# matrix_mixer_7eurorack.net
KiCad netlist of a schematic drawn in EAGLE
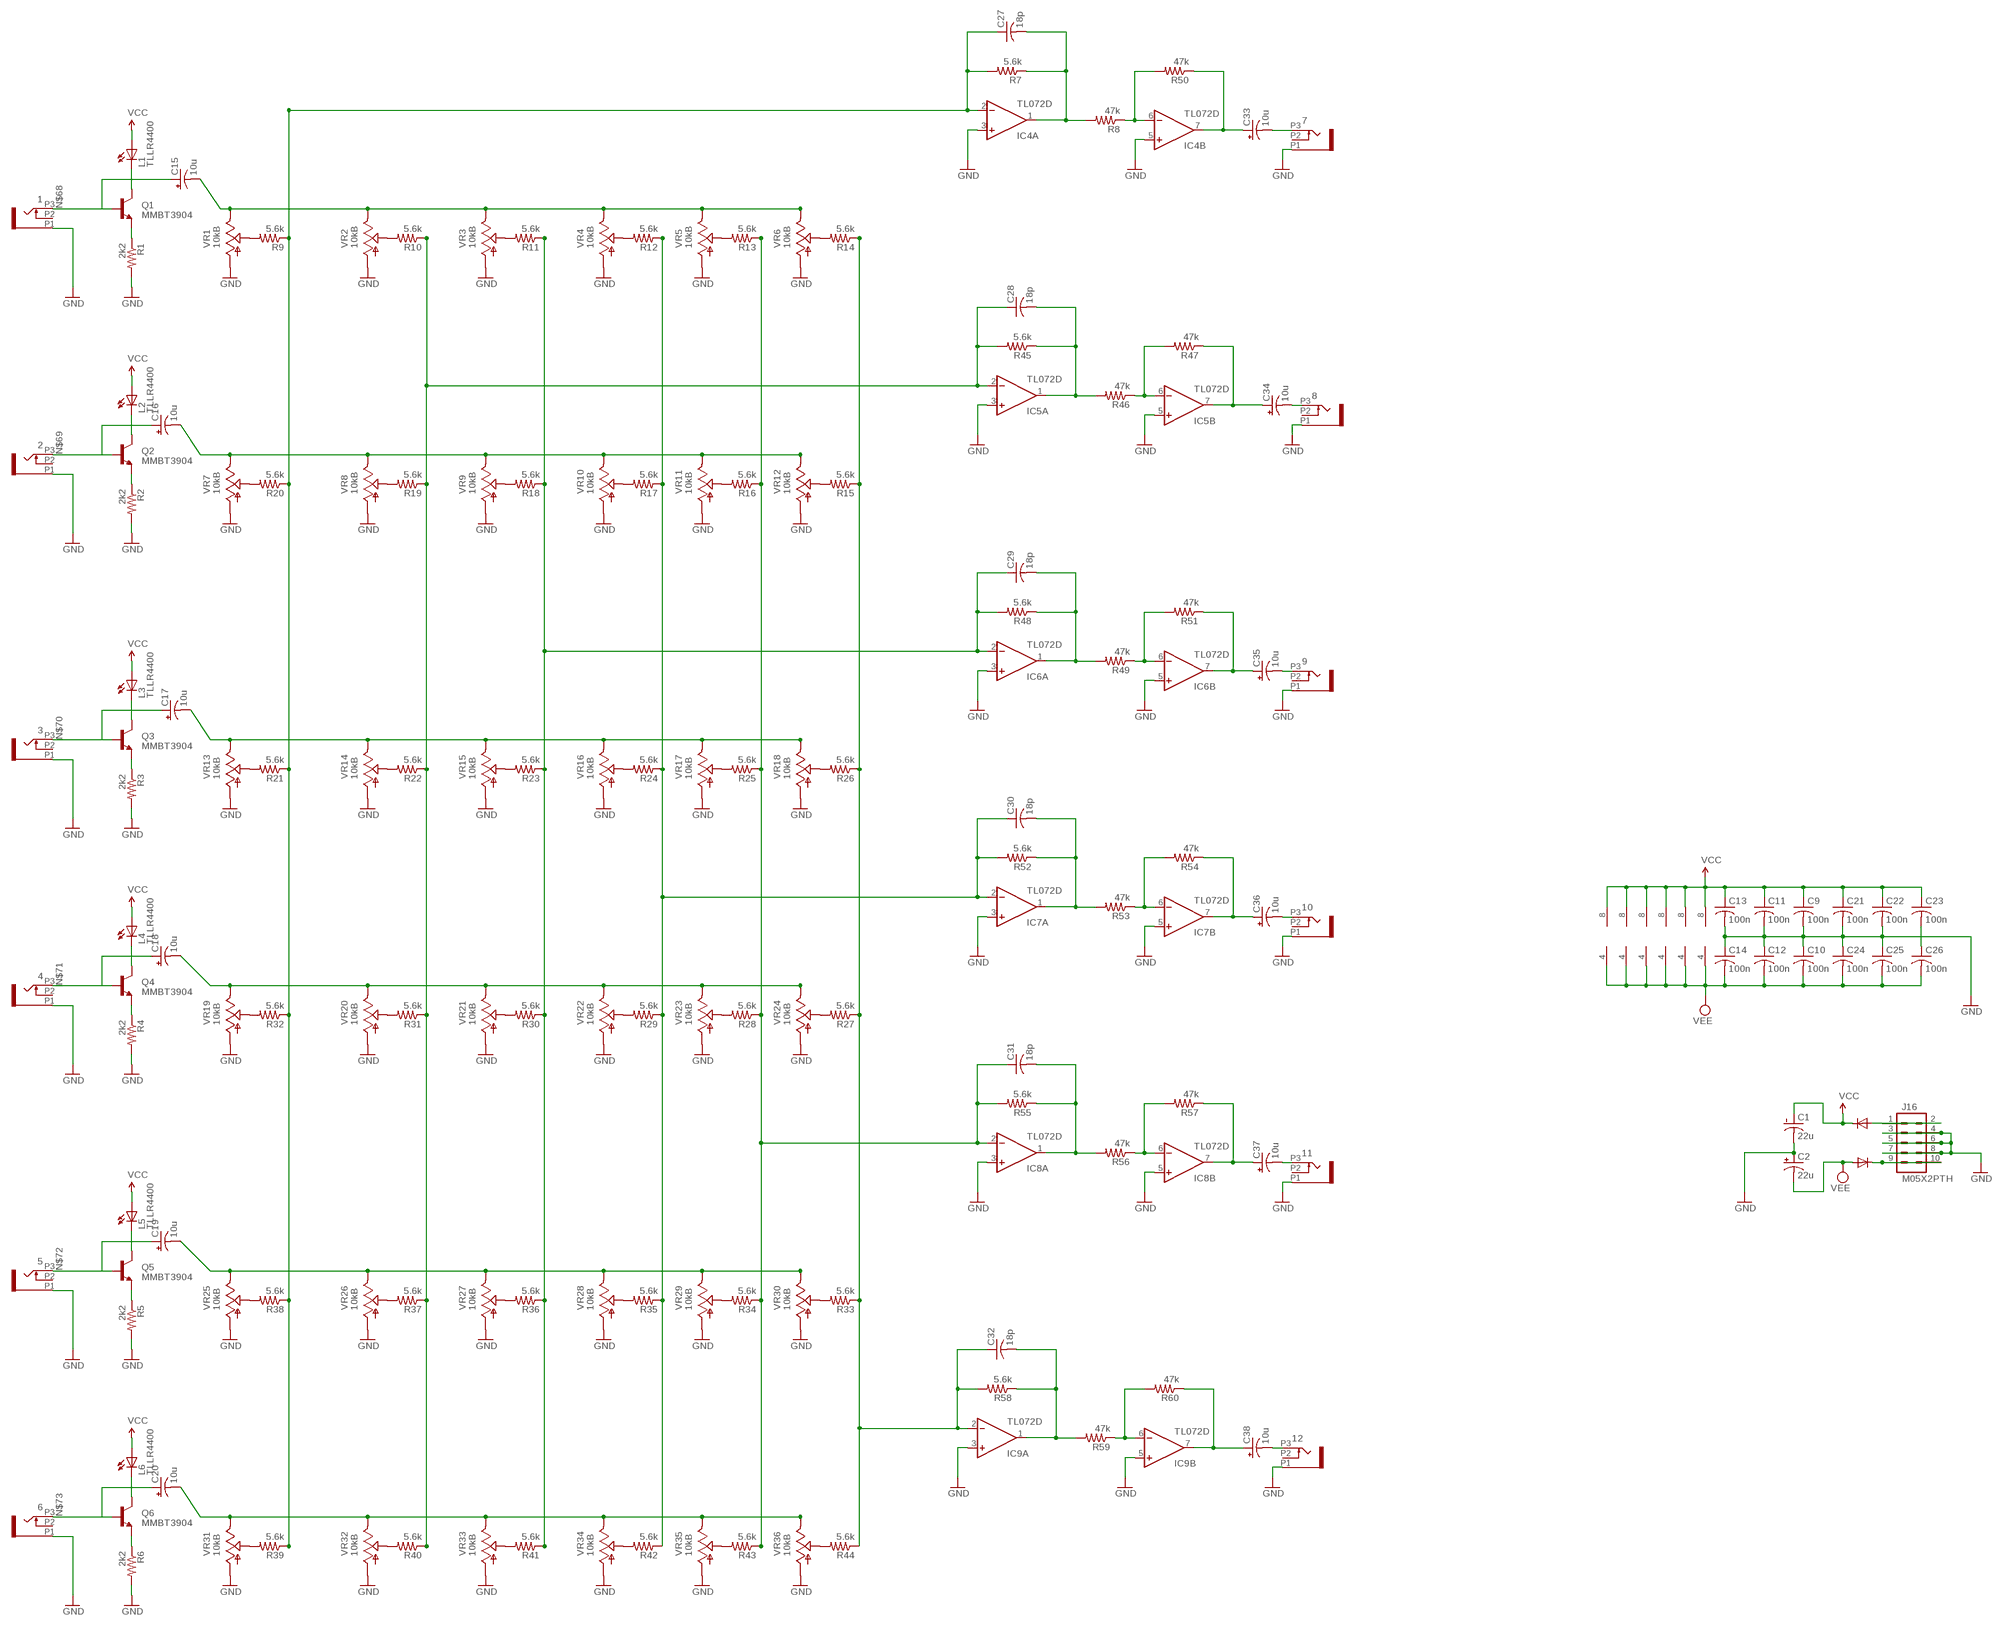
[diagram p0: schematic, sheet 1]

(export (version "E")
  (design (tool "Eeschema 10.0.6"))
  (components
    (comp (ref "1")
      (value "PJ301_THONKICONN6")
      (footprint "eagle-import:WQP_PJ_301M6")
      (libsource (lib "eagle-import") (part "PJ301_THONKICONN6"))
    )
    (comp (ref "2")
      (value "PJ301_THONKICONN6")
      (footprint "eagle-import:WQP_PJ_301M6")
      (libsource (lib "eagle-import") (part "PJ301_THONKICONN6"))
    )
    (comp (ref "3")
      (value "PJ301_THONKICONN6")
      (footprint "eagle-import:WQP_PJ_301M6")
      (libsource (lib "eagle-import") (part "PJ301_THONKICONN6"))
    )
    (comp (ref "4")
      (value "PJ301_THONKICONN6")
      (footprint "eagle-import:WQP_PJ_301M6")
      (libsource (lib "eagle-import") (part "PJ301_THONKICONN6"))
    )
    (comp (ref "5")
      (value "PJ301_THONKICONN6")
      (footprint "eagle-import:WQP_PJ_301M6")
      (libsource (lib "eagle-import") (part "PJ301_THONKICONN6"))
    )
    (comp (ref "6")
      (value "PJ301_THONKICONN6")
      (footprint "eagle-import:WQP_PJ_301M6")
      (libsource (lib "eagle-import") (part "PJ301_THONKICONN6"))
    )
    (comp (ref "7")
      (value "PJ301_THONKICONN6")
      (footprint "eagle-import:WQP_PJ_301M6")
      (libsource (lib "eagle-import") (part "PJ301_THONKICONN6"))
    )
    (comp (ref "8")
      (value "PJ301_THONKICONN6")
      (footprint "eagle-import:WQP_PJ_301M6")
      (libsource (lib "eagle-import") (part "PJ301_THONKICONN6"))
    )
    (comp (ref "9")
      (value "PJ301_THONKICONN6")
      (footprint "eagle-import:WQP_PJ_301M6")
      (libsource (lib "eagle-import") (part "PJ301_THONKICONN6"))
    )
    (comp (ref "10")
      (value "PJ301_THONKICONN6")
      (footprint "eagle-import:WQP_PJ_301M6")
      (libsource (lib "eagle-import") (part "PJ301_THONKICONN6"))
    )
    (comp (ref "11")
      (value "PJ301_THONKICONN6")
      (footprint "eagle-import:WQP_PJ_301M6")
      (libsource (lib "eagle-import") (part "PJ301_THONKICONN6"))
    )
    (comp (ref "12")
      (value "PJ301_THONKICONN6")
      (footprint "eagle-import:WQP_PJ_301M6")
      (libsource (lib "eagle-import") (part "PJ301_THONKICONN6"))
    )
    (comp (ref "C1")
      (value "22u")
      (footprint "eagle-import:PANASONIC_B")
      (libsource (lib "eagle-import") (part "CPOL-USB"))
    )
    (comp (ref "C2")
      (value "22u")
      (footprint "eagle-import:PANASONIC_B")
      (libsource (lib "eagle-import") (part "CPOL-USB"))
    )
    (comp (ref "C9")
      (value "100n")
      (footprint "eagle-import:C0603")
      (libsource (lib "eagle-import") (part "C-USC0603"))
    )
    (comp (ref "C10")
      (value "100n")
      (footprint "eagle-import:C0603")
      (libsource (lib "eagle-import") (part "C-USC0603"))
    )
    (comp (ref "C11")
      (value "100n")
      (footprint "eagle-import:C0603")
      (libsource (lib "eagle-import") (part "C-USC0603"))
    )
    (comp (ref "C12")
      (value "100n")
      (footprint "eagle-import:C0603")
      (libsource (lib "eagle-import") (part "C-USC0603"))
    )
    (comp (ref "C13")
      (value "100n")
      (footprint "eagle-import:C0603")
      (libsource (lib "eagle-import") (part "C-USC0603"))
    )
    (comp (ref "C14")
      (value "100n")
      (footprint "eagle-import:C0603")
      (libsource (lib "eagle-import") (part "C-USC0603"))
    )
    (comp (ref "C15")
      (value "10u")
      (footprint "eagle-import:PANASONIC_B")
      (libsource (lib "eagle-import") (part "CPOL-USB"))
    )
    (comp (ref "C16")
      (value "10u")
      (footprint "eagle-import:PANASONIC_B")
      (libsource (lib "eagle-import") (part "CPOL-USB"))
    )
    (comp (ref "C17")
      (value "10u")
      (footprint "eagle-import:PANASONIC_B")
      (libsource (lib "eagle-import") (part "CPOL-USB"))
    )
    (comp (ref "C18")
      (value "10u")
      (footprint "eagle-import:PANASONIC_B")
      (libsource (lib "eagle-import") (part "CPOL-USB"))
    )
    (comp (ref "C19")
      (value "10u")
      (footprint "eagle-import:PANASONIC_B")
      (libsource (lib "eagle-import") (part "CPOL-USB"))
    )
    (comp (ref "C20")
      (value "10u")
      (footprint "eagle-import:PANASONIC_B")
      (libsource (lib "eagle-import") (part "CPOL-USB"))
    )
    (comp (ref "C21")
      (value "100n")
      (footprint "eagle-import:C0603")
      (libsource (lib "eagle-import") (part "C-USC0603"))
    )
    (comp (ref "C22")
      (value "100n")
      (footprint "eagle-import:C0603")
      (libsource (lib "eagle-import") (part "C-USC0603"))
    )
    (comp (ref "C23")
      (value "100n")
      (footprint "eagle-import:C0603")
      (libsource (lib "eagle-import") (part "C-USC0603"))
    )
    (comp (ref "C24")
      (value "100n")
      (footprint "eagle-import:C0603")
      (libsource (lib "eagle-import") (part "C-USC0603"))
    )
    (comp (ref "C25")
      (value "100n")
      (footprint "eagle-import:C0603")
      (libsource (lib "eagle-import") (part "C-USC0603"))
    )
    (comp (ref "C26")
      (value "100n")
      (footprint "eagle-import:C0603")
      (libsource (lib "eagle-import") (part "C-USC0603"))
    )
    (comp (ref "C27")
      (value "18p")
      (footprint "eagle-import:C0603")
      (libsource (lib "eagle-import") (part "C-USC0603"))
    )
    (comp (ref "C28")
      (value "18p")
      (footprint "eagle-import:C0603")
      (libsource (lib "eagle-import") (part "C-USC0603"))
    )
    (comp (ref "C29")
      (value "18p")
      (footprint "eagle-import:C0603")
      (libsource (lib "eagle-import") (part "C-USC0603"))
    )
    (comp (ref "C30")
      (value "18p")
      (footprint "eagle-import:C0603")
      (libsource (lib "eagle-import") (part "C-USC0603"))
    )
    (comp (ref "C31")
      (value "18p")
      (footprint "eagle-import:C0603")
      (libsource (lib "eagle-import") (part "C-USC0603"))
    )
    (comp (ref "C32")
      (value "18p")
      (footprint "eagle-import:C0603")
      (libsource (lib "eagle-import") (part "C-USC0603"))
    )
    (comp (ref "C33")
      (value "10u")
      (footprint "eagle-import:PANASONIC_B")
      (libsource (lib "eagle-import") (part "CPOL-USB"))
    )
    (comp (ref "C34")
      (value "10u")
      (footprint "eagle-import:PANASONIC_B")
      (libsource (lib "eagle-import") (part "CPOL-USB"))
    )
    (comp (ref "C35")
      (value "10u")
      (footprint "eagle-import:PANASONIC_B")
      (libsource (lib "eagle-import") (part "CPOL-USB"))
    )
    (comp (ref "C36")
      (value "10u")
      (footprint "eagle-import:PANASONIC_B")
      (libsource (lib "eagle-import") (part "CPOL-USB"))
    )
    (comp (ref "C37")
      (value "10u")
      (footprint "eagle-import:PANASONIC_B")
      (libsource (lib "eagle-import") (part "CPOL-USB"))
    )
    (comp (ref "C38")
      (value "10u")
      (footprint "eagle-import:PANASONIC_B")
      (libsource (lib "eagle-import") (part "CPOL-USB"))
    )
    (comp (ref "D1")
      (value "1N5819HW")
      (footprint "eagle-import:SOD123")
      (libsource (lib "eagle-import") (part "DIODE-SOD123"))
    )
    (comp (ref "D2")
      (value "1N5819HW")
      (footprint "eagle-import:SOD123")
      (libsource (lib "eagle-import") (part "DIODE-SOD123"))
    )
    (comp (ref "IC4")
      (value "TL072D")
      (footprint "eagle-import:SO08")
      (libsource (lib "eagle-import") (part "TL072D"))
    )
    (comp (ref "IC5")
      (value "TL072D")
      (footprint "eagle-import:SO08")
      (libsource (lib "eagle-import") (part "TL072D"))
    )
    (comp (ref "IC6")
      (value "TL072D")
      (footprint "eagle-import:SO08")
      (libsource (lib "eagle-import") (part "TL072D"))
    )
    (comp (ref "IC7")
      (value "TL072D")
      (footprint "eagle-import:SO08")
      (libsource (lib "eagle-import") (part "TL072D"))
    )
    (comp (ref "IC8")
      (value "TL072D")
      (footprint "eagle-import:SO08")
      (libsource (lib "eagle-import") (part "TL072D"))
    )
    (comp (ref "IC9")
      (value "TL072D")
      (footprint "eagle-import:SO08")
      (libsource (lib "eagle-import") (part "TL072D"))
    )
    (comp (ref "J16")
      (value "M05X2PTH")
      (footprint "eagle-import:AVR_ICSP")
      (libsource (lib "eagle-import") (part "M05X2PTH"))
    )
    (comp (ref "L1")
      (value "TLLR4400")
      (footprint "eagle-import:LED3MM")
      (fields (field (name "MF") "VISHAY SEMICONDUCTOR"))
      (libsource (lib "eagle-import") (part "TLLR4400"))
    )
    (comp (ref "L2")
      (value "TLLR4400")
      (footprint "eagle-import:LED3MM")
      (fields (field (name "MF") "VISHAY SEMICONDUCTOR"))
      (libsource (lib "eagle-import") (part "TLLR4400"))
    )
    (comp (ref "L3")
      (value "TLLR4400")
      (footprint "eagle-import:LED3MM")
      (fields (field (name "MF") "VISHAY SEMICONDUCTOR"))
      (libsource (lib "eagle-import") (part "TLLR4400"))
    )
    (comp (ref "L4")
      (value "TLLR4400")
      (footprint "eagle-import:LED3MM")
      (fields (field (name "MF") "VISHAY SEMICONDUCTOR"))
      (libsource (lib "eagle-import") (part "TLLR4400"))
    )
    (comp (ref "L5")
      (value "TLLR4400")
      (footprint "eagle-import:LED3MM")
      (fields (field (name "MF") "VISHAY SEMICONDUCTOR"))
      (libsource (lib "eagle-import") (part "TLLR4400"))
    )
    (comp (ref "L6")
      (value "TLLR4400")
      (footprint "eagle-import:LED3MM")
      (fields (field (name "MF") "VISHAY SEMICONDUCTOR"))
      (libsource (lib "eagle-import") (part "TLLR4400"))
    )
    (comp (ref "Q1")
      (value "MMBT3904")
      (footprint "eagle-import:SOT23-BEC")
      (libsource (lib "eagle-import") (part "-NPN-SOT23-BECMMBT3904LT1"))
    )
    (comp (ref "Q2")
      (value "MMBT3904")
      (footprint "eagle-import:SOT23-BEC")
      (libsource (lib "eagle-import") (part "-NPN-SOT23-BECMMBT3904LT1"))
    )
    (comp (ref "Q3")
      (value "MMBT3904")
      (footprint "eagle-import:SOT23-BEC")
      (libsource (lib "eagle-import") (part "-NPN-SOT23-BECMMBT3904LT1"))
    )
    (comp (ref "Q4")
      (value "MMBT3904")
      (footprint "eagle-import:SOT23-BEC")
      (libsource (lib "eagle-import") (part "-NPN-SOT23-BECMMBT3904LT1"))
    )
    (comp (ref "Q5")
      (value "MMBT3904")
      (footprint "eagle-import:SOT23-BEC")
      (libsource (lib "eagle-import") (part "-NPN-SOT23-BECMMBT3904LT1"))
    )
    (comp (ref "Q6")
      (value "MMBT3904")
      (footprint "eagle-import:SOT23-BEC")
      (libsource (lib "eagle-import") (part "-NPN-SOT23-BECMMBT3904LT1"))
    )
    (comp (ref "R1")
      (value "2k2")
      (footprint "eagle-import:R0603")
      (libsource (lib "eagle-import") (part "R-US_R0603"))
    )
    (comp (ref "R2")
      (value "2k2")
      (footprint "eagle-import:R0603")
      (libsource (lib "eagle-import") (part "R-US_R0603"))
    )
    (comp (ref "R3")
      (value "2k2")
      (footprint "eagle-import:R0603")
      (libsource (lib "eagle-import") (part "R-US_R0603"))
    )
    (comp (ref "R4")
      (value "2k2")
      (footprint "eagle-import:R0603")
      (libsource (lib "eagle-import") (part "R-US_R0603"))
    )
    (comp (ref "R5")
      (value "2k2")
      (footprint "eagle-import:R0603")
      (libsource (lib "eagle-import") (part "R-US_R0603"))
    )
    (comp (ref "R6")
      (value "2k2")
      (footprint "eagle-import:R0603")
      (libsource (lib "eagle-import") (part "R-US_R0603"))
    )
    (comp (ref "R7")
      (value "5.6k")
      (footprint "eagle-import:R0603")
      (libsource (lib "eagle-import") (part "R-US_R0603"))
    )
    (comp (ref "R8")
      (value "47k")
      (footprint "eagle-import:R0603")
      (libsource (lib "eagle-import") (part "R-US_R0603"))
    )
    (comp (ref "R9")
      (value "5.6k")
      (footprint "eagle-import:R0603")
      (libsource (lib "eagle-import") (part "R-US_R0603"))
    )
    (comp (ref "R10")
      (value "5.6k")
      (footprint "eagle-import:R0603")
      (libsource (lib "eagle-import") (part "R-US_R0603"))
    )
    (comp (ref "R11")
      (value "5.6k")
      (footprint "eagle-import:R0603")
      (libsource (lib "eagle-import") (part "R-US_R0603"))
    )
    (comp (ref "R12")
      (value "5.6k")
      (footprint "eagle-import:R0603")
      (libsource (lib "eagle-import") (part "R-US_R0603"))
    )
    (comp (ref "R13")
      (value "5.6k")
      (footprint "eagle-import:R0603")
      (libsource (lib "eagle-import") (part "R-US_R0603"))
    )
    (comp (ref "R14")
      (value "5.6k")
      (footprint "eagle-import:R0603")
      (libsource (lib "eagle-import") (part "R-US_R0603"))
    )
    (comp (ref "R15")
      (value "5.6k")
      (footprint "eagle-import:R0603")
      (libsource (lib "eagle-import") (part "R-US_R0603"))
    )
    (comp (ref "R16")
      (value "5.6k")
      (footprint "eagle-import:R0603")
      (libsource (lib "eagle-import") (part "R-US_R0603"))
    )
    (comp (ref "R17")
      (value "5.6k")
      (footprint "eagle-import:R0603")
      (libsource (lib "eagle-import") (part "R-US_R0603"))
    )
    (comp (ref "R18")
      (value "5.6k")
      (footprint "eagle-import:R0603")
      (libsource (lib "eagle-import") (part "R-US_R0603"))
    )
    (comp (ref "R19")
      (value "5.6k")
      (footprint "eagle-import:R0603")
      (libsource (lib "eagle-import") (part "R-US_R0603"))
    )
    (comp (ref "R20")
      (value "5.6k")
      (footprint "eagle-import:R0603")
      (libsource (lib "eagle-import") (part "R-US_R0603"))
    )
    (comp (ref "R21")
      (value "5.6k")
      (footprint "eagle-import:R0603")
      (libsource (lib "eagle-import") (part "R-US_R0603"))
    )
    (comp (ref "R22")
      (value "5.6k")
      (footprint "eagle-import:R0603")
      (libsource (lib "eagle-import") (part "R-US_R0603"))
    )
    (comp (ref "R23")
      (value "5.6k")
      (footprint "eagle-import:R0603")
      (libsource (lib "eagle-import") (part "R-US_R0603"))
    )
    (comp (ref "R24")
      (value "5.6k")
      (footprint "eagle-import:R0603")
      (libsource (lib "eagle-import") (part "R-US_R0603"))
    )
    (comp (ref "R25")
      (value "5.6k")
      (footprint "eagle-import:R0603")
      (libsource (lib "eagle-import") (part "R-US_R0603"))
    )
    (comp (ref "R26")
      (value "5.6k")
      (footprint "eagle-import:R0603")
      (libsource (lib "eagle-import") (part "R-US_R0603"))
    )
    (comp (ref "R27")
      (value "5.6k")
      (footprint "eagle-import:R0603")
      (libsource (lib "eagle-import") (part "R-US_R0603"))
    )
    (comp (ref "R28")
      (value "5.6k")
      (footprint "eagle-import:R0603")
      (libsource (lib "eagle-import") (part "R-US_R0603"))
    )
    (comp (ref "R29")
      (value "5.6k")
      (footprint "eagle-import:R0603")
      (libsource (lib "eagle-import") (part "R-US_R0603"))
    )
    (comp (ref "R30")
      (value "5.6k")
      (footprint "eagle-import:R0603")
      (libsource (lib "eagle-import") (part "R-US_R0603"))
    )
    (comp (ref "R31")
      (value "5.6k")
      (footprint "eagle-import:R0603")
      (libsource (lib "eagle-import") (part "R-US_R0603"))
    )
    (comp (ref "R32")
      (value "5.6k")
      (footprint "eagle-import:R0603")
      (libsource (lib "eagle-import") (part "R-US_R0603"))
    )
    (comp (ref "R33")
      (value "5.6k")
      (footprint "eagle-import:R0603")
      (libsource (lib "eagle-import") (part "R-US_R0603"))
    )
    (comp (ref "R34")
      (value "5.6k")
      (footprint "eagle-import:R0603")
      (libsource (lib "eagle-import") (part "R-US_R0603"))
    )
    (comp (ref "R35")
      (value "5.6k")
      (footprint "eagle-import:R0603")
      (libsource (lib "eagle-import") (part "R-US_R0603"))
    )
    (comp (ref "R36")
      (value "5.6k")
      (footprint "eagle-import:R0603")
      (libsource (lib "eagle-import") (part "R-US_R0603"))
    )
    (comp (ref "R37")
      (value "5.6k")
      (footprint "eagle-import:R0603")
      (libsource (lib "eagle-import") (part "R-US_R0603"))
    )
    (comp (ref "R38")
      (value "5.6k")
      (footprint "eagle-import:R0603")
      (libsource (lib "eagle-import") (part "R-US_R0603"))
    )
    (comp (ref "R39")
      (value "5.6k")
      (footprint "eagle-import:R0603")
      (libsource (lib "eagle-import") (part "R-US_R0603"))
    )
    (comp (ref "R40")
      (value "5.6k")
      (footprint "eagle-import:R0603")
      (libsource (lib "eagle-import") (part "R-US_R0603"))
    )
    (comp (ref "R41")
      (value "5.6k")
      (footprint "eagle-import:R0603")
      (libsource (lib "eagle-import") (part "R-US_R0603"))
    )
    (comp (ref "R42")
      (value "5.6k")
      (footprint "eagle-import:R0603")
      (libsource (lib "eagle-import") (part "R-US_R0603"))
    )
    (comp (ref "R43")
      (value "5.6k")
      (footprint "eagle-import:R0603")
      (libsource (lib "eagle-import") (part "R-US_R0603"))
    )
    (comp (ref "R44")
      (value "5.6k")
      (footprint "eagle-import:R0603")
      (libsource (lib "eagle-import") (part "R-US_R0603"))
    )
    (comp (ref "R45")
      (value "5.6k")
      (footprint "eagle-import:R0603")
      (libsource (lib "eagle-import") (part "R-US_R0603"))
    )
    (comp (ref "R46")
      (value "47k")
      (footprint "eagle-import:R0603")
      (libsource (lib "eagle-import") (part "R-US_R0603"))
    )
    (comp (ref "R47")
      (value "47k")
      (footprint "eagle-import:R0603")
      (libsource (lib "eagle-import") (part "R-US_R0603"))
    )
    (comp (ref "R48")
      (value "5.6k")
      (footprint "eagle-import:R0603")
      (libsource (lib "eagle-import") (part "R-US_R0603"))
    )
    (comp (ref "R49")
      (value "47k")
      (footprint "eagle-import:R0603")
      (libsource (lib "eagle-import") (part "R-US_R0603"))
    )
    (comp (ref "R50")
      (value "47k")
      (footprint "eagle-import:R0603")
      (libsource (lib "eagle-import") (part "R-US_R0603"))
    )
    (comp (ref "R51")
      (value "47k")
      (footprint "eagle-import:R0603")
      (libsource (lib "eagle-import") (part "R-US_R0603"))
    )
    (comp (ref "R52")
      (value "5.6k")
      (footprint "eagle-import:R0603")
      (libsource (lib "eagle-import") (part "R-US_R0603"))
    )
    (comp (ref "R53")
      (value "47k")
      (footprint "eagle-import:R0603")
      (libsource (lib "eagle-import") (part "R-US_R0603"))
    )
    (comp (ref "R54")
      (value "47k")
      (footprint "eagle-import:R0603")
      (libsource (lib "eagle-import") (part "R-US_R0603"))
    )
    (comp (ref "R55")
      (value "5.6k")
      (footprint "eagle-import:R0603")
      (libsource (lib "eagle-import") (part "R-US_R0603"))
    )
    (comp (ref "R56")
      (value "47k")
      (footprint "eagle-import:R0603")
      (libsource (lib "eagle-import") (part "R-US_R0603"))
    )
    (comp (ref "R57")
      (value "47k")
      (footprint "eagle-import:R0603")
      (libsource (lib "eagle-import") (part "R-US_R0603"))
    )
    (comp (ref "R58")
      (value "5.6k")
      (footprint "eagle-import:R0603")
      (libsource (lib "eagle-import") (part "R-US_R0603"))
    )
    (comp (ref "R59")
      (value "47k")
      (footprint "eagle-import:R0603")
      (libsource (lib "eagle-import") (part "R-US_R0603"))
    )
    (comp (ref "R60")
      (value "47k")
      (footprint "eagle-import:R0603")
      (libsource (lib "eagle-import") (part "R-US_R0603"))
    )
    (comp (ref "VR1")
      (value "10kB")
      (footprint "eagle-import:ALPS_POT_VERTICAL_PS")
      (libsource (lib "eagle-import") (part "POT_USVERTICAL_PS"))
    )
    (comp (ref "VR2")
      (value "10kB")
      (footprint "eagle-import:ALPS_POT_VERTICAL_PS")
      (libsource (lib "eagle-import") (part "POT_USVERTICAL_PS"))
    )
    (comp (ref "VR3")
      (value "10kB")
      (footprint "eagle-import:ALPS_POT_VERTICAL_PS")
      (libsource (lib "eagle-import") (part "POT_USVERTICAL_PS"))
    )
    (comp (ref "VR4")
      (value "10kB")
      (footprint "eagle-import:ALPS_POT_VERTICAL_PS")
      (libsource (lib "eagle-import") (part "POT_USVERTICAL_PS"))
    )
    (comp (ref "VR5")
      (value "10kB")
      (footprint "eagle-import:ALPS_POT_VERTICAL_PS")
      (libsource (lib "eagle-import") (part "POT_USVERTICAL_PS"))
    )
    (comp (ref "VR6")
      (value "10kB")
      (footprint "eagle-import:ALPS_POT_VERTICAL_PS")
      (libsource (lib "eagle-import") (part "POT_USVERTICAL_PS"))
    )
    (comp (ref "VR7")
      (value "10kB")
      (footprint "eagle-import:ALPS_POT_VERTICAL_PS")
      (libsource (lib "eagle-import") (part "POT_USVERTICAL_PS"))
    )
    (comp (ref "VR8")
      (value "10kB")
      (footprint "eagle-import:ALPS_POT_VERTICAL_PS")
      (libsource (lib "eagle-import") (part "POT_USVERTICAL_PS"))
    )
    (comp (ref "VR9")
      (value "10kB")
      (footprint "eagle-import:ALPS_POT_VERTICAL_PS")
      (libsource (lib "eagle-import") (part "POT_USVERTICAL_PS"))
    )
    (comp (ref "VR10")
      (value "10kB")
      (footprint "eagle-import:ALPS_POT_VERTICAL_PS")
      (libsource (lib "eagle-import") (part "POT_USVERTICAL_PS"))
    )
    (comp (ref "VR11")
      (value "10kB")
      (footprint "eagle-import:ALPS_POT_VERTICAL_PS")
      (libsource (lib "eagle-import") (part "POT_USVERTICAL_PS"))
    )
    (comp (ref "VR12")
      (value "10kB")
      (footprint "eagle-import:ALPS_POT_VERTICAL_PS")
      (libsource (lib "eagle-import") (part "POT_USVERTICAL_PS"))
    )
    (comp (ref "VR13")
      (value "10kB")
      (footprint "eagle-import:ALPS_POT_VERTICAL_PS")
      (libsource (lib "eagle-import") (part "POT_USVERTICAL_PS"))
    )
    (comp (ref "VR14")
      (value "10kB")
      (footprint "eagle-import:ALPS_POT_VERTICAL_PS")
      (libsource (lib "eagle-import") (part "POT_USVERTICAL_PS"))
    )
    (comp (ref "VR15")
      (value "10kB")
      (footprint "eagle-import:ALPS_POT_VERTICAL_PS")
      (libsource (lib "eagle-import") (part "POT_USVERTICAL_PS"))
    )
    (comp (ref "VR16")
      (value "10kB")
      (footprint "eagle-import:ALPS_POT_VERTICAL_PS")
      (libsource (lib "eagle-import") (part "POT_USVERTICAL_PS"))
    )
    (comp (ref "VR17")
      (value "10kB")
      (footprint "eagle-import:ALPS_POT_VERTICAL_PS")
      (libsource (lib "eagle-import") (part "POT_USVERTICAL_PS"))
    )
    (comp (ref "VR18")
      (value "10kB")
      (footprint "eagle-import:ALPS_POT_VERTICAL_PS")
      (libsource (lib "eagle-import") (part "POT_USVERTICAL_PS"))
    )
    (comp (ref "VR19")
      (value "10kB")
      (footprint "eagle-import:ALPS_POT_VERTICAL_PS")
      (libsource (lib "eagle-import") (part "POT_USVERTICAL_PS"))
    )
    (comp (ref "VR20")
      (value "10kB")
      (footprint "eagle-import:ALPS_POT_VERTICAL_PS")
      (libsource (lib "eagle-import") (part "POT_USVERTICAL_PS"))
    )
    (comp (ref "VR21")
      (value "10kB")
      (footprint "eagle-import:ALPS_POT_VERTICAL_PS")
      (libsource (lib "eagle-import") (part "POT_USVERTICAL_PS"))
    )
    (comp (ref "VR22")
      (value "10kB")
      (footprint "eagle-import:ALPS_POT_VERTICAL_PS")
      (libsource (lib "eagle-import") (part "POT_USVERTICAL_PS"))
    )
    (comp (ref "VR23")
      (value "10kB")
      (footprint "eagle-import:ALPS_POT_VERTICAL_PS")
      (libsource (lib "eagle-import") (part "POT_USVERTICAL_PS"))
    )
    (comp (ref "VR24")
      (value "10kB")
      (footprint "eagle-import:ALPS_POT_VERTICAL_PS")
      (libsource (lib "eagle-import") (part "POT_USVERTICAL_PS"))
    )
    (comp (ref "VR25")
      (value "10kB")
      (footprint "eagle-import:ALPS_POT_VERTICAL_PS")
      (libsource (lib "eagle-import") (part "POT_USVERTICAL_PS"))
    )
    (comp (ref "VR26")
      (value "10kB")
      (footprint "eagle-import:ALPS_POT_VERTICAL_PS")
      (libsource (lib "eagle-import") (part "POT_USVERTICAL_PS"))
    )
    (comp (ref "VR27")
      (value "10kB")
      (footprint "eagle-import:ALPS_POT_VERTICAL_PS")
      (libsource (lib "eagle-import") (part "POT_USVERTICAL_PS"))
    )
    (comp (ref "VR28")
      (value "10kB")
      (footprint "eagle-import:ALPS_POT_VERTICAL_PS")
      (libsource (lib "eagle-import") (part "POT_USVERTICAL_PS"))
    )
    (comp (ref "VR29")
      (value "10kB")
      (footprint "eagle-import:ALPS_POT_VERTICAL_PS")
      (libsource (lib "eagle-import") (part "POT_USVERTICAL_PS"))
    )
    (comp (ref "VR30")
      (value "10kB")
      (footprint "eagle-import:ALPS_POT_VERTICAL_PS")
      (libsource (lib "eagle-import") (part "POT_USVERTICAL_PS"))
    )
    (comp (ref "VR31")
      (value "10kB")
      (footprint "eagle-import:ALPS_POT_VERTICAL_PS")
      (libsource (lib "eagle-import") (part "POT_USVERTICAL_PS"))
    )
    (comp (ref "VR32")
      (value "10kB")
      (footprint "eagle-import:ALPS_POT_VERTICAL_PS")
      (libsource (lib "eagle-import") (part "POT_USVERTICAL_PS"))
    )
    (comp (ref "VR33")
      (value "10kB")
      (footprint "eagle-import:ALPS_POT_VERTICAL_PS")
      (libsource (lib "eagle-import") (part "POT_USVERTICAL_PS"))
    )
    (comp (ref "VR34")
      (value "10kB")
      (footprint "eagle-import:ALPS_POT_VERTICAL_PS")
      (libsource (lib "eagle-import") (part "POT_USVERTICAL_PS"))
    )
    (comp (ref "VR35")
      (value "10kB")
      (footprint "eagle-import:ALPS_POT_VERTICAL_PS")
      (libsource (lib "eagle-import") (part "POT_USVERTICAL_PS"))
    )
    (comp (ref "VR36")
      (value "10kB")
      (footprint "eagle-import:ALPS_POT_VERTICAL_PS")
      (libsource (lib "eagle-import") (part "POT_USVERTICAL_PS"))
    )
  )
  (nets
    (net (code "1") (name "/N$68") (class "Default")
      (node (ref "1") (pin "P3") (pinfunction "3_P3") (pintype "passive"))
      (node (ref "C15") (pin "+") (pinfunction "+_+") (pintype "passive"))
      (node (ref "Q1") (pin "B") (pinfunction "B_B") (pintype "passive"))
    )
    (net (code "2") (name "/N$69") (class "Default")
      (node (ref "2") (pin "P3") (pinfunction "3_P3") (pintype "passive"))
      (node (ref "C16") (pin "+") (pinfunction "+_+") (pintype "passive"))
      (node (ref "Q2") (pin "B") (pinfunction "B_B") (pintype "passive"))
    )
    (net (code "3") (name "/N$70") (class "Default")
      (node (ref "3") (pin "P3") (pinfunction "3_P3") (pintype "passive"))
      (node (ref "C17") (pin "+") (pinfunction "+_+") (pintype "passive"))
      (node (ref "Q3") (pin "B") (pinfunction "B_B") (pintype "passive"))
    )
    (net (code "4") (name "/N$71") (class "Default")
      (node (ref "4") (pin "P3") (pinfunction "3_P3") (pintype "passive"))
      (node (ref "C18") (pin "+") (pinfunction "+_+") (pintype "passive"))
      (node (ref "Q4") (pin "B") (pinfunction "B_B") (pintype "passive"))
    )
    (net (code "5") (name "/N$72") (class "Default")
      (node (ref "5") (pin "P3") (pinfunction "3_P3") (pintype "passive"))
      (node (ref "C19") (pin "+") (pinfunction "+_+") (pintype "passive"))
      (node (ref "Q5") (pin "B") (pinfunction "B_B") (pintype "passive"))
    )
    (net (code "6") (name "/N$73") (class "Default")
      (node (ref "6") (pin "P3") (pinfunction "3_P3") (pintype "passive"))
      (node (ref "C20") (pin "+") (pinfunction "+_+") (pintype "passive"))
      (node (ref "Q6") (pin "B") (pinfunction "B_B") (pintype "passive"))
    )
    (net (code "7") (name "GND") (class "Default")
      (node (ref "1") (pin "P1") (pinfunction "1_P1") (pintype "passive"))
      (node (ref "10") (pin "P1") (pinfunction "1_P1") (pintype "passive"))
      (node (ref "11") (pin "P1") (pinfunction "1_P1") (pintype "passive"))
      (node (ref "12") (pin "P1") (pinfunction "1_P1") (pintype "passive"))
      (node (ref "2") (pin "P1") (pinfunction "1_P1") (pintype "passive"))
      (node (ref "3") (pin "P1") (pinfunction "1_P1") (pintype "passive"))
      (node (ref "4") (pin "P1") (pinfunction "1_P1") (pintype "passive"))
      (node (ref "5") (pin "P1") (pinfunction "1_P1") (pintype "passive"))
      (node (ref "6") (pin "P1") (pinfunction "1_P1") (pintype "passive"))
      (node (ref "7") (pin "P1") (pinfunction "1_P1") (pintype "passive"))
      (node (ref "8") (pin "P1") (pinfunction "1_P1") (pintype "passive"))
      (node (ref "9") (pin "P1") (pinfunction "1_P1") (pintype "passive"))
      (node (ref "C1") (pin "-") (pinfunction "-_-") (pintype "passive"))
      (node (ref "C10") (pin "1") (pinfunction "1_1") (pintype "passive"))
      (node (ref "C11") (pin "2") (pinfunction "2_2") (pintype "passive"))
      (node (ref "C12") (pin "1") (pinfunction "1_1") (pintype "passive"))
      (node (ref "C13") (pin "2") (pinfunction "2_2") (pintype "passive"))
      (node (ref "C14") (pin "1") (pinfunction "1_1") (pintype "passive"))
      (node (ref "C2") (pin "+") (pinfunction "+_+") (pintype "passive"))
      (node (ref "C21") (pin "2") (pinfunction "2_2") (pintype "passive"))
      (node (ref "C22") (pin "2") (pinfunction "2_2") (pintype "passive"))
      (node (ref "C23") (pin "2") (pinfunction "2_2") (pintype "passive"))
      (node (ref "C24") (pin "1") (pinfunction "1_1") (pintype "passive"))
      (node (ref "C25") (pin "1") (pinfunction "1_1") (pintype "passive"))
      (node (ref "C26") (pin "1") (pinfunction "1_1") (pintype "passive"))
      (node (ref "C9") (pin "2") (pinfunction "2_2") (pintype "passive"))
      (node (ref "IC4") (pin "3") (pinfunction "+IN_3") (pintype "input"))
      (node (ref "IC4") (pin "5") (pinfunction "+IN_5") (pintype "input"))
      (node (ref "IC5") (pin "3") (pinfunction "+IN_3") (pintype "input"))
      (node (ref "IC5") (pin "5") (pinfunction "+IN_5") (pintype "input"))
      (node (ref "IC6") (pin "3") (pinfunction "+IN_3") (pintype "input"))
      (node (ref "IC6") (pin "5") (pinfunction "+IN_5") (pintype "input"))
      (node (ref "IC7") (pin "3") (pinfunction "+IN_3") (pintype "input"))
      (node (ref "IC7") (pin "5") (pinfunction "+IN_5") (pintype "input"))
      (node (ref "IC8") (pin "3") (pinfunction "+IN_3") (pintype "input"))
      (node (ref "IC8") (pin "5") (pinfunction "+IN_5") (pintype "input"))
      (node (ref "IC9") (pin "3") (pinfunction "+IN_3") (pintype "input"))
      (node (ref "IC9") (pin "5") (pinfunction "+IN_5") (pintype "input"))
      (node (ref "J16") (pin "3") (pinfunction "3_3") (pintype "passive"))
      (node (ref "J16") (pin "4") (pinfunction "4_4") (pintype "passive"))
      (node (ref "J16") (pin "5") (pinfunction "5_5") (pintype "passive"))
      (node (ref "J16") (pin "6") (pinfunction "6_6") (pintype "passive"))
      (node (ref "J16") (pin "7") (pinfunction "7_7") (pintype "passive"))
      (node (ref "J16") (pin "8") (pinfunction "8_8") (pintype "passive"))
      (node (ref "R1") (pin "2") (pinfunction "2_2") (pintype "passive"))
      (node (ref "R2") (pin "2") (pinfunction "2_2") (pintype "passive"))
      (node (ref "R3") (pin "2") (pinfunction "2_2") (pintype "passive"))
      (node (ref "R4") (pin "2") (pinfunction "2_2") (pintype "passive"))
      (node (ref "R5") (pin "2") (pinfunction "2_2") (pintype "passive"))
      (node (ref "R6") (pin "2") (pinfunction "2_2") (pintype "passive"))
      (node (ref "VR1") (pin "P$3") (pinfunction "A_P$3") (pintype "passive"))
      (node (ref "VR10") (pin "P$3") (pinfunction "A_P$3") (pintype "passive"))
      (node (ref "VR11") (pin "P$3") (pinfunction "A_P$3") (pintype "passive"))
      (node (ref "VR12") (pin "P$3") (pinfunction "A_P$3") (pintype "passive"))
      (node (ref "VR13") (pin "P$3") (pinfunction "A_P$3") (pintype "passive"))
      (node (ref "VR14") (pin "P$3") (pinfunction "A_P$3") (pintype "passive"))
      (node (ref "VR15") (pin "P$3") (pinfunction "A_P$3") (pintype "passive"))
      (node (ref "VR16") (pin "P$3") (pinfunction "A_P$3") (pintype "passive"))
      (node (ref "VR17") (pin "P$3") (pinfunction "A_P$3") (pintype "passive"))
      (node (ref "VR18") (pin "P$3") (pinfunction "A_P$3") (pintype "passive"))
      (node (ref "VR19") (pin "P$3") (pinfunction "A_P$3") (pintype "passive"))
      (node (ref "VR2") (pin "P$3") (pinfunction "A_P$3") (pintype "passive"))
      (node (ref "VR20") (pin "P$3") (pinfunction "A_P$3") (pintype "passive"))
      (node (ref "VR21") (pin "P$3") (pinfunction "A_P$3") (pintype "passive"))
      (node (ref "VR22") (pin "P$3") (pinfunction "A_P$3") (pintype "passive"))
      (node (ref "VR23") (pin "P$3") (pinfunction "A_P$3") (pintype "passive"))
      (node (ref "VR24") (pin "P$3") (pinfunction "A_P$3") (pintype "passive"))
      (node (ref "VR25") (pin "P$3") (pinfunction "A_P$3") (pintype "passive"))
      (node (ref "VR26") (pin "P$3") (pinfunction "A_P$3") (pintype "passive"))
      (node (ref "VR27") (pin "P$3") (pinfunction "A_P$3") (pintype "passive"))
      (node (ref "VR28") (pin "P$3") (pinfunction "A_P$3") (pintype "passive"))
      (node (ref "VR29") (pin "P$3") (pinfunction "A_P$3") (pintype "passive"))
      (node (ref "VR3") (pin "P$3") (pinfunction "A_P$3") (pintype "passive"))
      (node (ref "VR30") (pin "P$3") (pinfunction "A_P$3") (pintype "passive"))
      (node (ref "VR31") (pin "P$3") (pinfunction "A_P$3") (pintype "passive"))
      (node (ref "VR32") (pin "P$3") (pinfunction "A_P$3") (pintype "passive"))
      (node (ref "VR33") (pin "P$3") (pinfunction "A_P$3") (pintype "passive"))
      (node (ref "VR34") (pin "P$3") (pinfunction "A_P$3") (pintype "passive"))
      (node (ref "VR35") (pin "P$3") (pinfunction "A_P$3") (pintype "passive"))
      (node (ref "VR36") (pin "P$3") (pinfunction "A_P$3") (pintype "passive"))
      (node (ref "VR4") (pin "P$3") (pinfunction "A_P$3") (pintype "passive"))
      (node (ref "VR5") (pin "P$3") (pinfunction "A_P$3") (pintype "passive"))
      (node (ref "VR6") (pin "P$3") (pinfunction "A_P$3") (pintype "passive"))
      (node (ref "VR7") (pin "P$3") (pinfunction "A_P$3") (pintype "passive"))
      (node (ref "VR8") (pin "P$3") (pinfunction "A_P$3") (pintype "passive"))
      (node (ref "VR9") (pin "P$3") (pinfunction "A_P$3") (pintype "passive"))
    )
    (net (code "8") (name "Net-(7-3)") (class "Default")
      (node (ref "7") (pin "P3") (pinfunction "3_P3") (pintype "passive"))
      (node (ref "C33") (pin "-") (pinfunction "-_-") (pintype "passive"))
    )
    (net (code "9") (name "Net-(8-3)") (class "Default")
      (node (ref "8") (pin "P3") (pinfunction "3_P3") (pintype "passive"))
      (node (ref "C34") (pin "-") (pinfunction "-_-") (pintype "passive"))
    )
    (net (code "10") (name "Net-(9-3)") (class "Default")
      (node (ref "9") (pin "P3") (pinfunction "3_P3") (pintype "passive"))
      (node (ref "C35") (pin "-") (pinfunction "-_-") (pintype "passive"))
    )
    (net (code "11") (name "Net-(10-3)") (class "Default")
      (node (ref "10") (pin "P3") (pinfunction "3_P3") (pintype "passive"))
      (node (ref "C36") (pin "-") (pinfunction "-_-") (pintype "passive"))
    )
    (net (code "12") (name "Net-(11-3)") (class "Default")
      (node (ref "11") (pin "P3") (pinfunction "3_P3") (pintype "passive"))
      (node (ref "C37") (pin "-") (pinfunction "-_-") (pintype "passive"))
    )
    (net (code "13") (name "Net-(12-3)") (class "Default")
      (node (ref "12") (pin "P3") (pinfunction "3_P3") (pintype "passive"))
      (node (ref "C38") (pin "-") (pinfunction "-_-") (pintype "passive"))
    )
    (net (code "14") (name "Net-(D1-PadA)") (class "Default")
      (node (ref "D1") (pin "A") (pinfunction "A_A") (pintype "passive"))
      (node (ref "J16") (pin "1") (pinfunction "1_1") (pintype "passive"))
      (node (ref "J16") (pin "2") (pinfunction "2_2") (pintype "passive"))
    )
    (net (code "15") (name "Net-(D2-PadC)") (class "Default")
      (node (ref "D2") (pin "C") (pinfunction "C_C") (pintype "passive"))
      (node (ref "J16") (pin "10") (pinfunction "10_10") (pintype "passive"))
      (node (ref "J16") (pin "9") (pinfunction "9_9") (pintype "passive"))
    )
    (net (code "16") (name "Net-(IC4A--IN)") (class "Default")
      (node (ref "C27") (pin "1") (pinfunction "1_1") (pintype "passive"))
      (node (ref "IC4") (pin "2") (pinfunction "-IN_2") (pintype "input"))
      (node (ref "R20") (pin "1") (pinfunction "1_1") (pintype "passive"))
      (node (ref "R21") (pin "1") (pinfunction "1_1") (pintype "passive"))
      (node (ref "R32") (pin "1") (pinfunction "1_1") (pintype "passive"))
      (node (ref "R38") (pin "1") (pinfunction "1_1") (pintype "passive"))
      (node (ref "R39") (pin "1") (pinfunction "1_1") (pintype "passive"))
      (node (ref "R7") (pin "2") (pinfunction "2_2") (pintype "passive"))
      (node (ref "R9") (pin "1") (pinfunction "1_1") (pintype "passive"))
    )
    (net (code "17") (name "Net-(IC4A-OUT)") (class "Default")
      (node (ref "C27") (pin "2") (pinfunction "2_2") (pintype "passive"))
      (node (ref "IC4") (pin "1") (pinfunction "OUT_1") (pintype "output"))
      (node (ref "R7") (pin "1") (pinfunction "1_1") (pintype "passive"))
      (node (ref "R8") (pin "2") (pinfunction "2_2") (pintype "passive"))
    )
    (net (code "18") (name "Net-(IC4B--IN)") (class "Default")
      (node (ref "IC4") (pin "6") (pinfunction "-IN_6") (pintype "input"))
      (node (ref "R50") (pin "2") (pinfunction "2_2") (pintype "passive"))
      (node (ref "R8") (pin "1") (pinfunction "1_1") (pintype "passive"))
    )
    (net (code "19") (name "Net-(IC4B-OUT)") (class "Default")
      (node (ref "C33") (pin "+") (pinfunction "+_+") (pintype "passive"))
      (node (ref "IC4") (pin "7") (pinfunction "OUT_7") (pintype "output"))
      (node (ref "R50") (pin "1") (pinfunction "1_1") (pintype "passive"))
    )
    (net (code "20") (name "Net-(IC5A--IN)") (class "Default")
      (node (ref "C28") (pin "1") (pinfunction "1_1") (pintype "passive"))
      (node (ref "IC5") (pin "2") (pinfunction "-IN_2") (pintype "input"))
      (node (ref "R10") (pin "1") (pinfunction "1_1") (pintype "passive"))
      (node (ref "R19") (pin "1") (pinfunction "1_1") (pintype "passive"))
      (node (ref "R22") (pin "1") (pinfunction "1_1") (pintype "passive"))
      (node (ref "R31") (pin "1") (pinfunction "1_1") (pintype "passive"))
      (node (ref "R37") (pin "1") (pinfunction "1_1") (pintype "passive"))
      (node (ref "R40") (pin "1") (pinfunction "1_1") (pintype "passive"))
      (node (ref "R45") (pin "2") (pinfunction "2_2") (pintype "passive"))
    )
    (net (code "21") (name "Net-(IC5A-OUT)") (class "Default")
      (node (ref "C28") (pin "2") (pinfunction "2_2") (pintype "passive"))
      (node (ref "IC5") (pin "1") (pinfunction "OUT_1") (pintype "output"))
      (node (ref "R45") (pin "1") (pinfunction "1_1") (pintype "passive"))
      (node (ref "R46") (pin "2") (pinfunction "2_2") (pintype "passive"))
    )
    (net (code "22") (name "Net-(IC5B--IN)") (class "Default")
      (node (ref "IC5") (pin "6") (pinfunction "-IN_6") (pintype "input"))
      (node (ref "R46") (pin "1") (pinfunction "1_1") (pintype "passive"))
      (node (ref "R47") (pin "2") (pinfunction "2_2") (pintype "passive"))
    )
    (net (code "23") (name "Net-(IC5B-OUT)") (class "Default")
      (node (ref "C34") (pin "+") (pinfunction "+_+") (pintype "passive"))
      (node (ref "IC5") (pin "7") (pinfunction "OUT_7") (pintype "output"))
      (node (ref "R47") (pin "1") (pinfunction "1_1") (pintype "passive"))
    )
    (net (code "24") (name "Net-(IC6A--IN)") (class "Default")
      (node (ref "C29") (pin "1") (pinfunction "1_1") (pintype "passive"))
      (node (ref "IC6") (pin "2") (pinfunction "-IN_2") (pintype "input"))
      (node (ref "R11") (pin "1") (pinfunction "1_1") (pintype "passive"))
      (node (ref "R18") (pin "1") (pinfunction "1_1") (pintype "passive"))
      (node (ref "R23") (pin "1") (pinfunction "1_1") (pintype "passive"))
      (node (ref "R30") (pin "1") (pinfunction "1_1") (pintype "passive"))
      (node (ref "R36") (pin "1") (pinfunction "1_1") (pintype "passive"))
      (node (ref "R41") (pin "1") (pinfunction "1_1") (pintype "passive"))
      (node (ref "R48") (pin "2") (pinfunction "2_2") (pintype "passive"))
    )
    (net (code "25") (name "Net-(IC6A-OUT)") (class "Default")
      (node (ref "C29") (pin "2") (pinfunction "2_2") (pintype "passive"))
      (node (ref "IC6") (pin "1") (pinfunction "OUT_1") (pintype "output"))
      (node (ref "R48") (pin "1") (pinfunction "1_1") (pintype "passive"))
      (node (ref "R49") (pin "2") (pinfunction "2_2") (pintype "passive"))
    )
    (net (code "26") (name "Net-(IC6B--IN)") (class "Default")
      (node (ref "IC6") (pin "6") (pinfunction "-IN_6") (pintype "input"))
      (node (ref "R49") (pin "1") (pinfunction "1_1") (pintype "passive"))
      (node (ref "R51") (pin "2") (pinfunction "2_2") (pintype "passive"))
    )
    (net (code "27") (name "Net-(IC6B-OUT)") (class "Default")
      (node (ref "C35") (pin "+") (pinfunction "+_+") (pintype "passive"))
      (node (ref "IC6") (pin "7") (pinfunction "OUT_7") (pintype "output"))
      (node (ref "R51") (pin "1") (pinfunction "1_1") (pintype "passive"))
    )
    (net (code "28") (name "Net-(IC7A--IN)") (class "Default")
      (node (ref "C30") (pin "1") (pinfunction "1_1") (pintype "passive"))
      (node (ref "IC7") (pin "2") (pinfunction "-IN_2") (pintype "input"))
      (node (ref "R12") (pin "1") (pinfunction "1_1") (pintype "passive"))
      (node (ref "R17") (pin "1") (pinfunction "1_1") (pintype "passive"))
      (node (ref "R24") (pin "1") (pinfunction "1_1") (pintype "passive"))
      (node (ref "R29") (pin "1") (pinfunction "1_1") (pintype "passive"))
      (node (ref "R35") (pin "1") (pinfunction "1_1") (pintype "passive"))
      (node (ref "R42") (pin "1") (pinfunction "1_1") (pintype "passive"))
      (node (ref "R52") (pin "2") (pinfunction "2_2") (pintype "passive"))
    )
    (net (code "29") (name "Net-(IC7A-OUT)") (class "Default")
      (node (ref "C30") (pin "2") (pinfunction "2_2") (pintype "passive"))
      (node (ref "IC7") (pin "1") (pinfunction "OUT_1") (pintype "output"))
      (node (ref "R52") (pin "1") (pinfunction "1_1") (pintype "passive"))
      (node (ref "R53") (pin "2") (pinfunction "2_2") (pintype "passive"))
    )
    (net (code "30") (name "Net-(IC7B--IN)") (class "Default")
      (node (ref "IC7") (pin "6") (pinfunction "-IN_6") (pintype "input"))
      (node (ref "R53") (pin "1") (pinfunction "1_1") (pintype "passive"))
      (node (ref "R54") (pin "2") (pinfunction "2_2") (pintype "passive"))
    )
    (net (code "31") (name "Net-(IC7B-OUT)") (class "Default")
      (node (ref "C36") (pin "+") (pinfunction "+_+") (pintype "passive"))
      (node (ref "IC7") (pin "7") (pinfunction "OUT_7") (pintype "output"))
      (node (ref "R54") (pin "1") (pinfunction "1_1") (pintype "passive"))
    )
    (net (code "32") (name "Net-(IC8A--IN)") (class "Default")
      (node (ref "C31") (pin "1") (pinfunction "1_1") (pintype "passive"))
      (node (ref "IC8") (pin "2") (pinfunction "-IN_2") (pintype "input"))
      (node (ref "R13") (pin "1") (pinfunction "1_1") (pintype "passive"))
      (node (ref "R16") (pin "1") (pinfunction "1_1") (pintype "passive"))
      (node (ref "R25") (pin "1") (pinfunction "1_1") (pintype "passive"))
      (node (ref "R28") (pin "1") (pinfunction "1_1") (pintype "passive"))
      (node (ref "R34") (pin "1") (pinfunction "1_1") (pintype "passive"))
      (node (ref "R43") (pin "1") (pinfunction "1_1") (pintype "passive"))
      (node (ref "R55") (pin "2") (pinfunction "2_2") (pintype "passive"))
    )
    (net (code "33") (name "Net-(IC8A-OUT)") (class "Default")
      (node (ref "C31") (pin "2") (pinfunction "2_2") (pintype "passive"))
      (node (ref "IC8") (pin "1") (pinfunction "OUT_1") (pintype "output"))
      (node (ref "R55") (pin "1") (pinfunction "1_1") (pintype "passive"))
      (node (ref "R56") (pin "2") (pinfunction "2_2") (pintype "passive"))
    )
    (net (code "34") (name "Net-(IC8B--IN)") (class "Default")
      (node (ref "IC8") (pin "6") (pinfunction "-IN_6") (pintype "input"))
      (node (ref "R56") (pin "1") (pinfunction "1_1") (pintype "passive"))
      (node (ref "R57") (pin "2") (pinfunction "2_2") (pintype "passive"))
    )
    (net (code "35") (name "Net-(IC8B-OUT)") (class "Default")
      (node (ref "C37") (pin "+") (pinfunction "+_+") (pintype "passive"))
      (node (ref "IC8") (pin "7") (pinfunction "OUT_7") (pintype "output"))
      (node (ref "R57") (pin "1") (pinfunction "1_1") (pintype "passive"))
    )
    (net (code "36") (name "Net-(IC9A--IN)") (class "Default")
      (node (ref "C32") (pin "1") (pinfunction "1_1") (pintype "passive"))
      (node (ref "IC9") (pin "2") (pinfunction "-IN_2") (pintype "input"))
      (node (ref "R14") (pin "1") (pinfunction "1_1") (pintype "passive"))
      (node (ref "R15") (pin "1") (pinfunction "1_1") (pintype "passive"))
      (node (ref "R26") (pin "1") (pinfunction "1_1") (pintype "passive"))
      (node (ref "R27") (pin "1") (pinfunction "1_1") (pintype "passive"))
      (node (ref "R33") (pin "1") (pinfunction "1_1") (pintype "passive"))
      (node (ref "R44") (pin "1") (pinfunction "1_1") (pintype "passive"))
      (node (ref "R58") (pin "2") (pinfunction "2_2") (pintype "passive"))
    )
    (net (code "37") (name "Net-(IC9A-OUT)") (class "Default")
      (node (ref "C32") (pin "2") (pinfunction "2_2") (pintype "passive"))
      (node (ref "IC9") (pin "1") (pinfunction "OUT_1") (pintype "output"))
      (node (ref "R58") (pin "1") (pinfunction "1_1") (pintype "passive"))
      (node (ref "R59") (pin "2") (pinfunction "2_2") (pintype "passive"))
    )
    (net (code "38") (name "Net-(IC9B--IN)") (class "Default")
      (node (ref "IC9") (pin "6") (pinfunction "-IN_6") (pintype "input"))
      (node (ref "R59") (pin "1") (pinfunction "1_1") (pintype "passive"))
      (node (ref "R60") (pin "2") (pinfunction "2_2") (pintype "passive"))
    )
    (net (code "39") (name "Net-(IC9B-OUT)") (class "Default")
      (node (ref "C38") (pin "+") (pinfunction "+_+") (pintype "passive"))
      (node (ref "IC9") (pin "7") (pinfunction "OUT_7") (pintype "output"))
      (node (ref "R60") (pin "1") (pinfunction "1_1") (pintype "passive"))
    )
    (net (code "40") (name "Net-(L1-C)") (class "Default")
      (node (ref "L1") (pin "K") (pinfunction "C_K") (pintype "passive"))
      (node (ref "Q1") (pin "C") (pinfunction "C_C") (pintype "passive"))
    )
    (net (code "41") (name "Net-(L2-C)") (class "Default")
      (node (ref "L2") (pin "K") (pinfunction "C_K") (pintype "passive"))
      (node (ref "Q2") (pin "C") (pinfunction "C_C") (pintype "passive"))
    )
    (net (code "42") (name "Net-(L3-C)") (class "Default")
      (node (ref "L3") (pin "K") (pinfunction "C_K") (pintype "passive"))
      (node (ref "Q3") (pin "C") (pinfunction "C_C") (pintype "passive"))
    )
    (net (code "43") (name "Net-(L4-C)") (class "Default")
      (node (ref "L4") (pin "K") (pinfunction "C_K") (pintype "passive"))
      (node (ref "Q4") (pin "C") (pinfunction "C_C") (pintype "passive"))
    )
    (net (code "44") (name "Net-(L5-C)") (class "Default")
      (node (ref "L5") (pin "K") (pinfunction "C_K") (pintype "passive"))
      (node (ref "Q5") (pin "C") (pinfunction "C_C") (pintype "passive"))
    )
    (net (code "45") (name "Net-(L6-C)") (class "Default")
      (node (ref "L6") (pin "K") (pinfunction "C_K") (pintype "passive"))
      (node (ref "Q6") (pin "C") (pinfunction "C_C") (pintype "passive"))
    )
    (net (code "46") (name "Net-(Q1-PadE)") (class "Default")
      (node (ref "Q1") (pin "E") (pinfunction "E_E") (pintype "passive"))
      (node (ref "R1") (pin "1") (pinfunction "1_1") (pintype "passive"))
    )
    (net (code "47") (name "Net-(Q2-PadE)") (class "Default")
      (node (ref "Q2") (pin "E") (pinfunction "E_E") (pintype "passive"))
      (node (ref "R2") (pin "1") (pinfunction "1_1") (pintype "passive"))
    )
    (net (code "48") (name "Net-(Q3-PadE)") (class "Default")
      (node (ref "Q3") (pin "E") (pinfunction "E_E") (pintype "passive"))
      (node (ref "R3") (pin "1") (pinfunction "1_1") (pintype "passive"))
    )
    (net (code "49") (name "Net-(Q4-PadE)") (class "Default")
      (node (ref "Q4") (pin "E") (pinfunction "E_E") (pintype "passive"))
      (node (ref "R4") (pin "1") (pinfunction "1_1") (pintype "passive"))
    )
    (net (code "50") (name "Net-(Q5-PadE)") (class "Default")
      (node (ref "Q5") (pin "E") (pinfunction "E_E") (pintype "passive"))
      (node (ref "R5") (pin "1") (pinfunction "1_1") (pintype "passive"))
    )
    (net (code "51") (name "Net-(Q6-PadE)") (class "Default")
      (node (ref "Q6") (pin "E") (pinfunction "E_E") (pintype "passive"))
      (node (ref "R6") (pin "1") (pinfunction "1_1") (pintype "passive"))
    )
    (net (code "52") (name "Net-(VR1-E)") (class "Default")
      (node (ref "C15") (pin "-") (pinfunction "-_-") (pintype "passive"))
      (node (ref "VR1") (pin "P$1") (pinfunction "E_P$1") (pintype "passive"))
      (node (ref "VR2") (pin "P$1") (pinfunction "E_P$1") (pintype "passive"))
      (node (ref "VR3") (pin "P$1") (pinfunction "E_P$1") (pintype "passive"))
      (node (ref "VR4") (pin "P$1") (pinfunction "E_P$1") (pintype "passive"))
      (node (ref "VR5") (pin "P$1") (pinfunction "E_P$1") (pintype "passive"))
      (node (ref "VR6") (pin "P$1") (pinfunction "E_P$1") (pintype "passive"))
    )
    (net (code "53") (name "Net-(VR1-S)") (class "Default")
      (node (ref "R9") (pin "2") (pinfunction "2_2") (pintype "passive"))
      (node (ref "VR1") (pin "P$2") (pinfunction "S_P$2") (pintype "passive"))
    )
    (net (code "54") (name "Net-(VR2-S)") (class "Default")
      (node (ref "R10") (pin "2") (pinfunction "2_2") (pintype "passive"))
      (node (ref "VR2") (pin "P$2") (pinfunction "S_P$2") (pintype "passive"))
    )
    (net (code "55") (name "Net-(VR3-S)") (class "Default")
      (node (ref "R11") (pin "2") (pinfunction "2_2") (pintype "passive"))
      (node (ref "VR3") (pin "P$2") (pinfunction "S_P$2") (pintype "passive"))
    )
    (net (code "56") (name "Net-(VR4-S)") (class "Default")
      (node (ref "R12") (pin "2") (pinfunction "2_2") (pintype "passive"))
      (node (ref "VR4") (pin "P$2") (pinfunction "S_P$2") (pintype "passive"))
    )
    (net (code "57") (name "Net-(VR5-S)") (class "Default")
      (node (ref "R13") (pin "2") (pinfunction "2_2") (pintype "passive"))
      (node (ref "VR5") (pin "P$2") (pinfunction "S_P$2") (pintype "passive"))
    )
    (net (code "58") (name "Net-(VR6-S)") (class "Default")
      (node (ref "R14") (pin "2") (pinfunction "2_2") (pintype "passive"))
      (node (ref "VR6") (pin "P$2") (pinfunction "S_P$2") (pintype "passive"))
    )
    (net (code "59") (name "Net-(VR7-S)") (class "Default")
      (node (ref "R20") (pin "2") (pinfunction "2_2") (pintype "passive"))
      (node (ref "VR7") (pin "P$2") (pinfunction "S_P$2") (pintype "passive"))
    )
    (net (code "60") (name "Net-(VR8-S)") (class "Default")
      (node (ref "R19") (pin "2") (pinfunction "2_2") (pintype "passive"))
      (node (ref "VR8") (pin "P$2") (pinfunction "S_P$2") (pintype "passive"))
    )
    (net (code "61") (name "Net-(VR9-S)") (class "Default")
      (node (ref "R18") (pin "2") (pinfunction "2_2") (pintype "passive"))
      (node (ref "VR9") (pin "P$2") (pinfunction "S_P$2") (pintype "passive"))
    )
    (net (code "62") (name "Net-(VR10-E)") (class "Default")
      (node (ref "C16") (pin "-") (pinfunction "-_-") (pintype "passive"))
      (node (ref "VR10") (pin "P$1") (pinfunction "E_P$1") (pintype "passive"))
      (node (ref "VR11") (pin "P$1") (pinfunction "E_P$1") (pintype "passive"))
      (node (ref "VR12") (pin "P$1") (pinfunction "E_P$1") (pintype "passive"))
      (node (ref "VR7") (pin "P$1") (pinfunction "E_P$1") (pintype "passive"))
      (node (ref "VR8") (pin "P$1") (pinfunction "E_P$1") (pintype "passive"))
      (node (ref "VR9") (pin "P$1") (pinfunction "E_P$1") (pintype "passive"))
    )
    (net (code "63") (name "Net-(VR10-S)") (class "Default")
      (node (ref "R17") (pin "2") (pinfunction "2_2") (pintype "passive"))
      (node (ref "VR10") (pin "P$2") (pinfunction "S_P$2") (pintype "passive"))
    )
    (net (code "64") (name "Net-(VR11-S)") (class "Default")
      (node (ref "R16") (pin "2") (pinfunction "2_2") (pintype "passive"))
      (node (ref "VR11") (pin "P$2") (pinfunction "S_P$2") (pintype "passive"))
    )
    (net (code "65") (name "Net-(VR12-S)") (class "Default")
      (node (ref "R15") (pin "2") (pinfunction "2_2") (pintype "passive"))
      (node (ref "VR12") (pin "P$2") (pinfunction "S_P$2") (pintype "passive"))
    )
    (net (code "66") (name "Net-(VR13-E)") (class "Default")
      (node (ref "C17") (pin "-") (pinfunction "-_-") (pintype "passive"))
      (node (ref "VR13") (pin "P$1") (pinfunction "E_P$1") (pintype "passive"))
      (node (ref "VR14") (pin "P$1") (pinfunction "E_P$1") (pintype "passive"))
      (node (ref "VR15") (pin "P$1") (pinfunction "E_P$1") (pintype "passive"))
      (node (ref "VR16") (pin "P$1") (pinfunction "E_P$1") (pintype "passive"))
      (node (ref "VR17") (pin "P$1") (pinfunction "E_P$1") (pintype "passive"))
      (node (ref "VR18") (pin "P$1") (pinfunction "E_P$1") (pintype "passive"))
    )
    (net (code "67") (name "Net-(VR13-S)") (class "Default")
      (node (ref "R21") (pin "2") (pinfunction "2_2") (pintype "passive"))
      (node (ref "VR13") (pin "P$2") (pinfunction "S_P$2") (pintype "passive"))
    )
    (net (code "68") (name "Net-(VR14-S)") (class "Default")
      (node (ref "R22") (pin "2") (pinfunction "2_2") (pintype "passive"))
      (node (ref "VR14") (pin "P$2") (pinfunction "S_P$2") (pintype "passive"))
    )
    (net (code "69") (name "Net-(VR15-S)") (class "Default")
      (node (ref "R23") (pin "2") (pinfunction "2_2") (pintype "passive"))
      (node (ref "VR15") (pin "P$2") (pinfunction "S_P$2") (pintype "passive"))
    )
    (net (code "70") (name "Net-(VR16-S)") (class "Default")
      (node (ref "R24") (pin "2") (pinfunction "2_2") (pintype "passive"))
      (node (ref "VR16") (pin "P$2") (pinfunction "S_P$2") (pintype "passive"))
    )
    (net (code "71") (name "Net-(VR17-S)") (class "Default")
      (node (ref "R25") (pin "2") (pinfunction "2_2") (pintype "passive"))
      (node (ref "VR17") (pin "P$2") (pinfunction "S_P$2") (pintype "passive"))
    )
    (net (code "72") (name "Net-(VR18-S)") (class "Default")
      (node (ref "R26") (pin "2") (pinfunction "2_2") (pintype "passive"))
      (node (ref "VR18") (pin "P$2") (pinfunction "S_P$2") (pintype "passive"))
    )
    (net (code "73") (name "Net-(VR19-E)") (class "Default")
      (node (ref "C18") (pin "-") (pinfunction "-_-") (pintype "passive"))
      (node (ref "VR19") (pin "P$1") (pinfunction "E_P$1") (pintype "passive"))
      (node (ref "VR20") (pin "P$1") (pinfunction "E_P$1") (pintype "passive"))
      (node (ref "VR21") (pin "P$1") (pinfunction "E_P$1") (pintype "passive"))
      (node (ref "VR22") (pin "P$1") (pinfunction "E_P$1") (pintype "passive"))
      (node (ref "VR23") (pin "P$1") (pinfunction "E_P$1") (pintype "passive"))
      (node (ref "VR24") (pin "P$1") (pinfunction "E_P$1") (pintype "passive"))
    )
    (net (code "74") (name "Net-(VR19-S)") (class "Default")
      (node (ref "R32") (pin "2") (pinfunction "2_2") (pintype "passive"))
      (node (ref "VR19") (pin "P$2") (pinfunction "S_P$2") (pintype "passive"))
    )
    (net (code "75") (name "Net-(VR20-S)") (class "Default")
      (node (ref "R31") (pin "2") (pinfunction "2_2") (pintype "passive"))
      (node (ref "VR20") (pin "P$2") (pinfunction "S_P$2") (pintype "passive"))
    )
    (net (code "76") (name "Net-(VR21-S)") (class "Default")
      (node (ref "R30") (pin "2") (pinfunction "2_2") (pintype "passive"))
      (node (ref "VR21") (pin "P$2") (pinfunction "S_P$2") (pintype "passive"))
    )
    (net (code "77") (name "Net-(VR22-S)") (class "Default")
      (node (ref "R29") (pin "2") (pinfunction "2_2") (pintype "passive"))
      (node (ref "VR22") (pin "P$2") (pinfunction "S_P$2") (pintype "passive"))
    )
    (net (code "78") (name "Net-(VR23-S)") (class "Default")
      (node (ref "R28") (pin "2") (pinfunction "2_2") (pintype "passive"))
      (node (ref "VR23") (pin "P$2") (pinfunction "S_P$2") (pintype "passive"))
    )
    (net (code "79") (name "Net-(VR24-S)") (class "Default")
      (node (ref "R27") (pin "2") (pinfunction "2_2") (pintype "passive"))
      (node (ref "VR24") (pin "P$2") (pinfunction "S_P$2") (pintype "passive"))
    )
    (net (code "80") (name "Net-(VR25-E)") (class "Default")
      (node (ref "C19") (pin "-") (pinfunction "-_-") (pintype "passive"))
      (node (ref "VR25") (pin "P$1") (pinfunction "E_P$1") (pintype "passive"))
      (node (ref "VR26") (pin "P$1") (pinfunction "E_P$1") (pintype "passive"))
      (node (ref "VR27") (pin "P$1") (pinfunction "E_P$1") (pintype "passive"))
      (node (ref "VR28") (pin "P$1") (pinfunction "E_P$1") (pintype "passive"))
      (node (ref "VR29") (pin "P$1") (pinfunction "E_P$1") (pintype "passive"))
      (node (ref "VR30") (pin "P$1") (pinfunction "E_P$1") (pintype "passive"))
    )
    (net (code "81") (name "Net-(VR25-S)") (class "Default")
      (node (ref "R38") (pin "2") (pinfunction "2_2") (pintype "passive"))
      (node (ref "VR25") (pin "P$2") (pinfunction "S_P$2") (pintype "passive"))
    )
    (net (code "82") (name "Net-(VR26-S)") (class "Default")
      (node (ref "R37") (pin "2") (pinfunction "2_2") (pintype "passive"))
      (node (ref "VR26") (pin "P$2") (pinfunction "S_P$2") (pintype "passive"))
    )
    (net (code "83") (name "Net-(VR27-S)") (class "Default")
      (node (ref "R36") (pin "2") (pinfunction "2_2") (pintype "passive"))
      (node (ref "VR27") (pin "P$2") (pinfunction "S_P$2") (pintype "passive"))
    )
    (net (code "84") (name "Net-(VR28-S)") (class "Default")
      (node (ref "R35") (pin "2") (pinfunction "2_2") (pintype "passive"))
      (node (ref "VR28") (pin "P$2") (pinfunction "S_P$2") (pintype "passive"))
    )
    (net (code "85") (name "Net-(VR29-S)") (class "Default")
      (node (ref "R34") (pin "2") (pinfunction "2_2") (pintype "passive"))
      (node (ref "VR29") (pin "P$2") (pinfunction "S_P$2") (pintype "passive"))
    )
    (net (code "86") (name "Net-(VR30-S)") (class "Default")
      (node (ref "R33") (pin "2") (pinfunction "2_2") (pintype "passive"))
      (node (ref "VR30") (pin "P$2") (pinfunction "S_P$2") (pintype "passive"))
    )
    (net (code "87") (name "Net-(VR31-E)") (class "Default")
      (node (ref "C20") (pin "-") (pinfunction "-_-") (pintype "passive"))
      (node (ref "VR31") (pin "P$1") (pinfunction "E_P$1") (pintype "passive"))
      (node (ref "VR32") (pin "P$1") (pinfunction "E_P$1") (pintype "passive"))
      (node (ref "VR33") (pin "P$1") (pinfunction "E_P$1") (pintype "passive"))
      (node (ref "VR34") (pin "P$1") (pinfunction "E_P$1") (pintype "passive"))
      (node (ref "VR35") (pin "P$1") (pinfunction "E_P$1") (pintype "passive"))
      (node (ref "VR36") (pin "P$1") (pinfunction "E_P$1") (pintype "passive"))
    )
    (net (code "88") (name "Net-(VR31-S)") (class "Default")
      (node (ref "R39") (pin "2") (pinfunction "2_2") (pintype "passive"))
      (node (ref "VR31") (pin "P$2") (pinfunction "S_P$2") (pintype "passive"))
    )
    (net (code "89") (name "Net-(VR32-S)") (class "Default")
      (node (ref "R40") (pin "2") (pinfunction "2_2") (pintype "passive"))
      (node (ref "VR32") (pin "P$2") (pinfunction "S_P$2") (pintype "passive"))
    )
    (net (code "90") (name "Net-(VR33-S)") (class "Default")
      (node (ref "R41") (pin "2") (pinfunction "2_2") (pintype "passive"))
      (node (ref "VR33") (pin "P$2") (pinfunction "S_P$2") (pintype "passive"))
    )
    (net (code "91") (name "Net-(VR34-S)") (class "Default")
      (node (ref "R42") (pin "2") (pinfunction "2_2") (pintype "passive"))
      (node (ref "VR34") (pin "P$2") (pinfunction "S_P$2") (pintype "passive"))
    )
    (net (code "92") (name "Net-(VR35-S)") (class "Default")
      (node (ref "R43") (pin "2") (pinfunction "2_2") (pintype "passive"))
      (node (ref "VR35") (pin "P$2") (pinfunction "S_P$2") (pintype "passive"))
    )
    (net (code "93") (name "Net-(VR36-S)") (class "Default")
      (node (ref "R44") (pin "2") (pinfunction "2_2") (pintype "passive"))
      (node (ref "VR36") (pin "P$2") (pinfunction "S_P$2") (pintype "passive"))
    )
    (net (code "94") (name "VCC") (class "Default")
      (node (ref "C1") (pin "+") (pinfunction "+_+") (pintype "passive"))
      (node (ref "C11") (pin "1") (pinfunction "1_1") (pintype "passive"))
      (node (ref "C13") (pin "1") (pinfunction "1_1") (pintype "passive"))
      (node (ref "C21") (pin "1") (pinfunction "1_1") (pintype "passive"))
      (node (ref "C22") (pin "1") (pinfunction "1_1") (pintype "passive"))
      (node (ref "C23") (pin "1") (pinfunction "1_1") (pintype "passive"))
      (node (ref "C9") (pin "1") (pinfunction "1_1") (pintype "passive"))
      (node (ref "D1") (pin "C") (pinfunction "C_C") (pintype "passive"))
      (node (ref "IC4") (pin "8") (pinfunction "V+_8") (pintype "power_in"))
      (node (ref "IC5") (pin "8") (pinfunction "V+_8") (pintype "power_in"))
      (node (ref "IC6") (pin "8") (pinfunction "V+_8") (pintype "power_in"))
      (node (ref "IC7") (pin "8") (pinfunction "V+_8") (pintype "power_in"))
      (node (ref "IC8") (pin "8") (pinfunction "V+_8") (pintype "power_in"))
      (node (ref "IC9") (pin "8") (pinfunction "V+_8") (pintype "power_in"))
      (node (ref "L1") (pin "A") (pinfunction "A_A") (pintype "passive"))
      (node (ref "L2") (pin "A") (pinfunction "A_A") (pintype "passive"))
      (node (ref "L3") (pin "A") (pinfunction "A_A") (pintype "passive"))
      (node (ref "L4") (pin "A") (pinfunction "A_A") (pintype "passive"))
      (node (ref "L5") (pin "A") (pinfunction "A_A") (pintype "passive"))
      (node (ref "L6") (pin "A") (pinfunction "A_A") (pintype "passive"))
    )
    (net (code "95") (name "VEE") (class "Default")
      (node (ref "C10") (pin "2") (pinfunction "2_2") (pintype "passive"))
      (node (ref "C12") (pin "2") (pinfunction "2_2") (pintype "passive"))
      (node (ref "C14") (pin "2") (pinfunction "2_2") (pintype "passive"))
      (node (ref "C2") (pin "-") (pinfunction "-_-") (pintype "passive"))
      (node (ref "C24") (pin "2") (pinfunction "2_2") (pintype "passive"))
      (node (ref "C25") (pin "2") (pinfunction "2_2") (pintype "passive"))
      (node (ref "C26") (pin "2") (pinfunction "2_2") (pintype "passive"))
      (node (ref "D2") (pin "A") (pinfunction "A_A") (pintype "passive"))
      (node (ref "IC4") (pin "4") (pinfunction "V-_4") (pintype "power_in"))
      (node (ref "IC5") (pin "4") (pinfunction "V-_4") (pintype "power_in"))
      (node (ref "IC6") (pin "4") (pinfunction "V-_4") (pintype "power_in"))
      (node (ref "IC7") (pin "4") (pinfunction "V-_4") (pintype "power_in"))
      (node (ref "IC8") (pin "4") (pinfunction "V-_4") (pintype "power_in"))
      (node (ref "IC9") (pin "4") (pinfunction "V-_4") (pintype "power_in"))
    )
    (net (code "96") (name "unconnected-(1-2-PadP2)") (class "Default")
      (node (ref "1") (pin "P2") (pinfunction "2_P2") (pintype "passive"))
    )
    (net (code "97") (name "unconnected-(2-2-PadP2)") (class "Default")
      (node (ref "2") (pin "P2") (pinfunction "2_P2") (pintype "passive"))
    )
    (net (code "98") (name "unconnected-(3-2-PadP2)") (class "Default")
      (node (ref "3") (pin "P2") (pinfunction "2_P2") (pintype "passive"))
    )
    (net (code "99") (name "unconnected-(4-2-PadP2)") (class "Default")
      (node (ref "4") (pin "P2") (pinfunction "2_P2") (pintype "passive"))
    )
    (net (code "100") (name "unconnected-(5-2-PadP2)") (class "Default")
      (node (ref "5") (pin "P2") (pinfunction "2_P2") (pintype "passive"))
    )
    (net (code "101") (name "unconnected-(6-2-PadP2)") (class "Default")
      (node (ref "6") (pin "P2") (pinfunction "2_P2") (pintype "passive"))
    )
    (net (code "102") (name "unconnected-(7-2-PadP2)") (class "Default")
      (node (ref "7") (pin "P2") (pinfunction "2_P2") (pintype "passive"))
    )
    (net (code "103") (name "unconnected-(8-2-PadP2)") (class "Default")
      (node (ref "8") (pin "P2") (pinfunction "2_P2") (pintype "passive"))
    )
    (net (code "104") (name "unconnected-(9-2-PadP2)") (class "Default")
      (node (ref "9") (pin "P2") (pinfunction "2_P2") (pintype "passive"))
    )
    (net (code "105") (name "unconnected-(10-2-PadP2)") (class "Default")
      (node (ref "10") (pin "P2") (pinfunction "2_P2") (pintype "passive"))
    )
    (net (code "106") (name "unconnected-(11-2-PadP2)") (class "Default")
      (node (ref "11") (pin "P2") (pinfunction "2_P2") (pintype "passive"))
    )
    (net (code "107") (name "unconnected-(12-2-PadP2)") (class "Default")
      (node (ref "12") (pin "P2") (pinfunction "2_P2") (pintype "passive"))
    )
  )
)
